# schematic.net
KiCad netlist of a schematic drawn in EAGLE
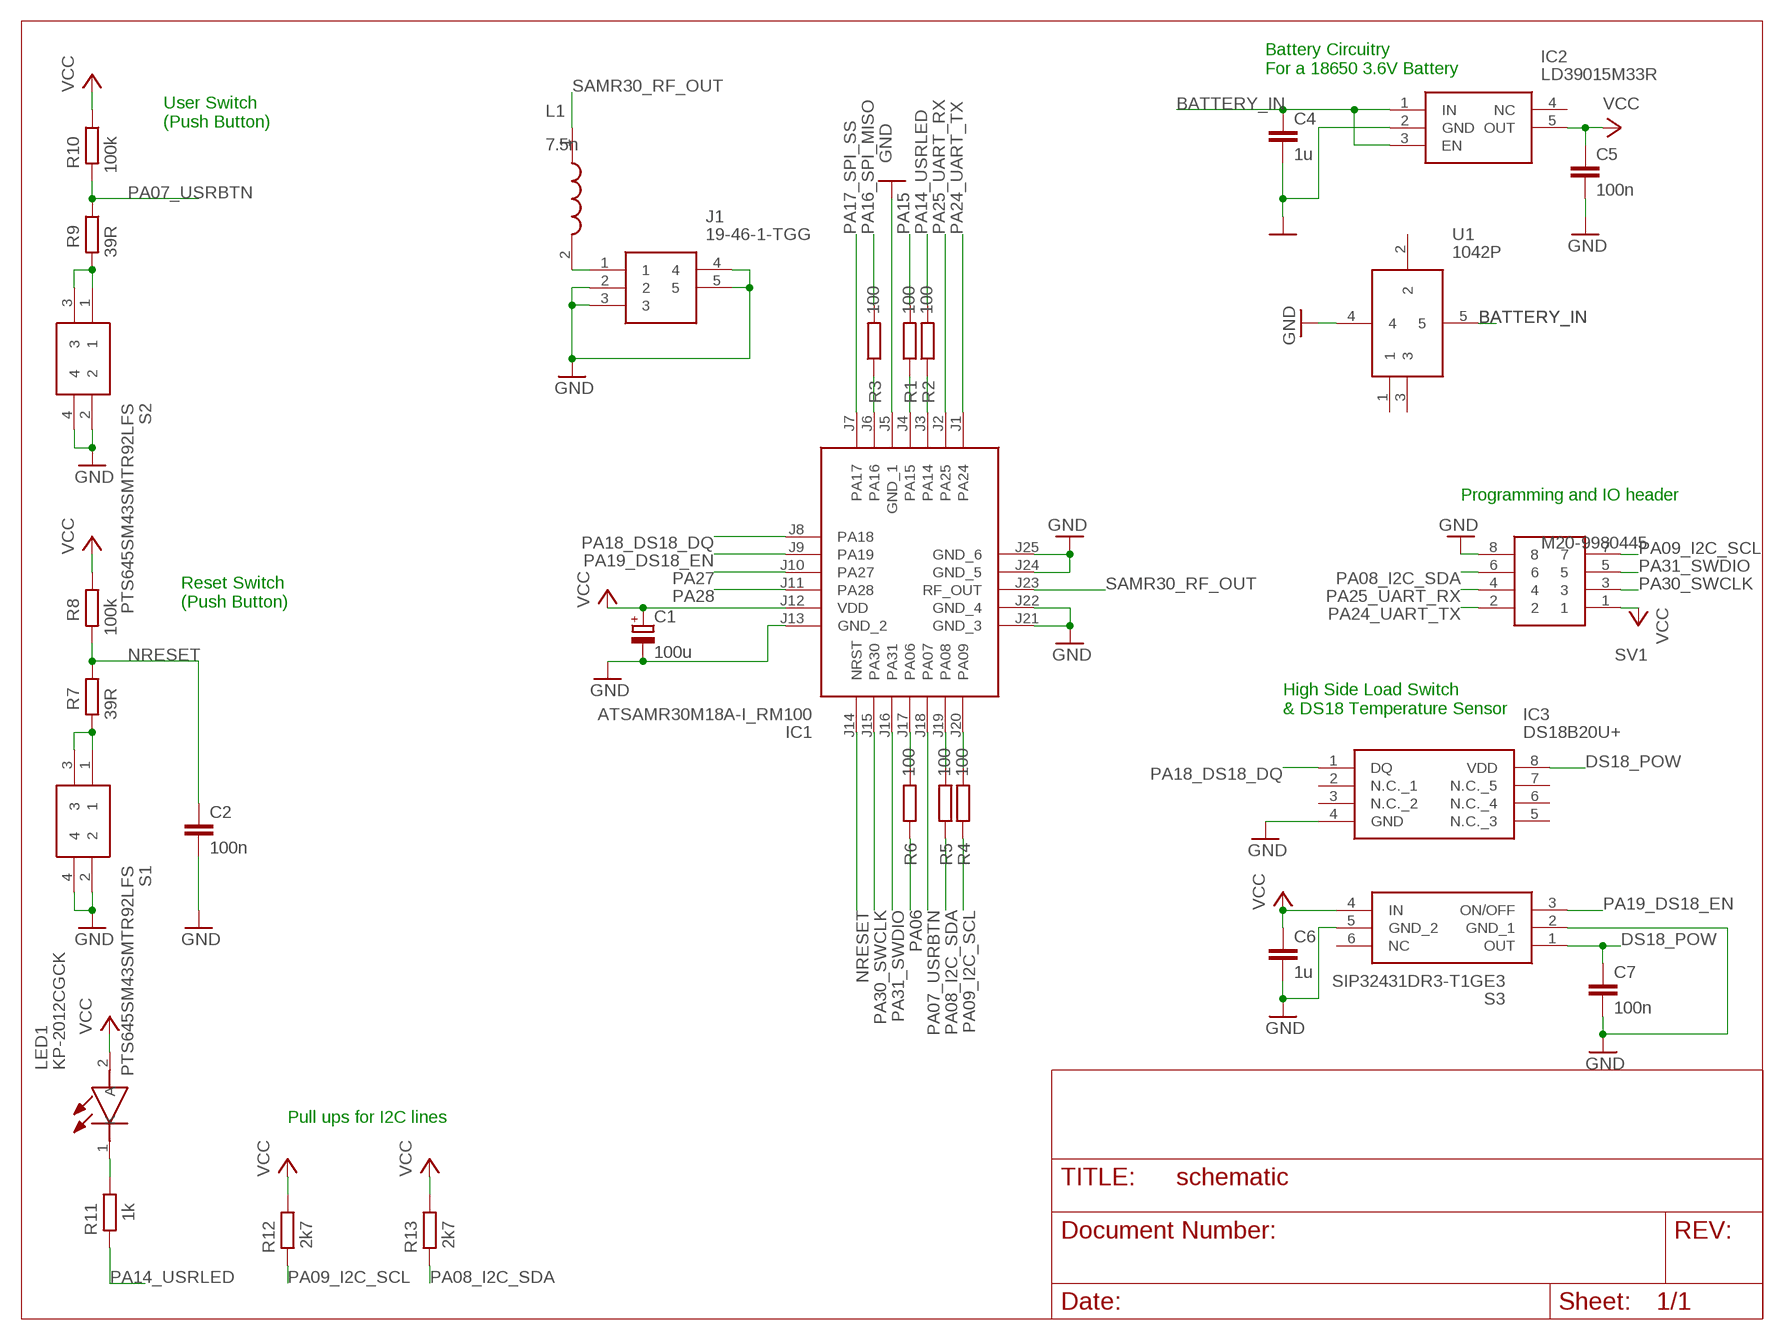
[diagram p0: schematic, sheet 1]

(export (version "E")
  (design (tool "Eeschema 10.0.6"))
  (components
    (comp (ref "C1")
      (value "100u")
      (footprint "eagle-import:A_3216-18W")
      (libsource (lib "eagle-import") (part "CPOL-EUA/3216-18W"))
    )
    (comp (ref "C2")
      (value "100n")
      (footprint "eagle-import:C0805")
      (libsource (lib "eagle-import") (part "C-EUC0805"))
    )
    (comp (ref "C4")
      (value "1u")
      (footprint "eagle-import:C0805")
      (libsource (lib "eagle-import") (part "C-EUC0805"))
    )
    (comp (ref "C5")
      (value "100n")
      (footprint "eagle-import:C0805")
      (libsource (lib "eagle-import") (part "C-EUC0805"))
    )
    (comp (ref "C6")
      (value "1u")
      (footprint "eagle-import:C0805")
      (libsource (lib "eagle-import") (part "C-EUC0805"))
    )
    (comp (ref "C7")
      (value "100n")
      (footprint "eagle-import:C0805")
      (libsource (lib "eagle-import") (part "C-EUC0805"))
    )
    (comp (ref "IC1")
      (value "ATSAMR30M18A-I_RM100")
      (footprint "eagle-import:ATSAMR30M18AIRM100")
      (fields
        (field (name "MANUFACTURER_PART_NUMBER") "ATSAMR30M18A-I/RM100")
        (field (name "MOUSER_PART_NUMBER") "556-AMR30M18AIRM100")
        (field (name "RS_PART_NUMBER") "1840450")
      )
      (libsource (lib "eagle-import") (part "ATSAMR30M18A-I_RM100"))
    )
    (comp (ref "IC2")
      (value "LD39015M33R")
      (footprint "eagle-import:SOT95P280X145-5N")
      (fields
        (field (name "MOUSER_PART_NUMBER") "511-LD39015M33R")
        (field (name "RS_PART_NUMBER") "7958965P")
      )
      (libsource (lib "eagle-import") (part "LD39015M33R"))
    )
    (comp (ref "IC3")
      (value "DS18B20U+")
      (footprint "eagle-import:SOP65P490X110-8N")
      (fields (field (name "MOUSER_PART_NUMBER") "700-DS18B20U"))
      (libsource (lib "eagle-import") (part "DS18B20U+"))
    )
    (comp (ref "J1")
      (value "19-46-1-TGG")
      (footprint "eagle-import:19-46-1-TGG_1")
      (libsource (lib "eagle-import") (part "19-46-1-TGG"))
    )
    (comp (ref "L1")
      (value "7.5n")
      (footprint "eagle-import:INDC1006X60N")
      (fields
        (field (name "MANUFACTURER_PART_NUMBER") "MHQ1005P10NJT")
        (field (name "MOUSER_PART_NUMBER") "810-MHQ1005P10NJT")
        (field (name "RS_PART_NUMBER") "7958243P")
      )
      (libsource (lib "eagle-import") (part "MHQ1005P10NJT"))
    )
    (comp (ref "LED1")
      (value "KP-2012CGCK")
      (footprint "eagle-import:LEDC2012X110N")
      (fields (field (name "RS_PART_NUMBER") "8610037P"))
      (libsource (lib "eagle-import") (part "KP-2012CGCK"))
    )
    (comp (ref "R1")
      (value "100")
      (footprint "eagle-import:R0603")
      (libsource (lib "eagle-import") (part "R-EU_R0603"))
    )
    (comp (ref "R2")
      (value "100")
      (footprint "eagle-import:R0603")
      (libsource (lib "eagle-import") (part "R-EU_R0603"))
    )
    (comp (ref "R3")
      (value "100")
      (footprint "eagle-import:R0603")
      (libsource (lib "eagle-import") (part "R-EU_R0603"))
    )
    (comp (ref "R4")
      (value "100")
      (footprint "eagle-import:R0603")
      (libsource (lib "eagle-import") (part "R-EU_R0603"))
    )
    (comp (ref "R5")
      (value "100")
      (footprint "eagle-import:R0603")
      (libsource (lib "eagle-import") (part "R-EU_R0603"))
    )
    (comp (ref "R6")
      (value "100")
      (footprint "eagle-import:R0603")
      (libsource (lib "eagle-import") (part "R-EU_R0603"))
    )
    (comp (ref "R7")
      (value "39R")
      (footprint "eagle-import:R0603")
      (libsource (lib "eagle-import") (part "R-EU_R0603"))
    )
    (comp (ref "R8")
      (value "100k")
      (footprint "eagle-import:R0603")
      (libsource (lib "eagle-import") (part "R-EU_R0603"))
    )
    (comp (ref "R9")
      (value "39R")
      (footprint "eagle-import:R0603")
      (libsource (lib "eagle-import") (part "R-EU_R0603"))
    )
    (comp (ref "R10")
      (value "100k")
      (footprint "eagle-import:R0603")
      (libsource (lib "eagle-import") (part "R-EU_R0603"))
    )
    (comp (ref "R11")
      (value "1k")
      (footprint "eagle-import:R0603")
      (libsource (lib "eagle-import") (part "R-EU_R0603"))
    )
    (comp (ref "R12")
      (value "2k7")
      (footprint "eagle-import:R0603")
      (libsource (lib "eagle-import") (part "R-EU_R0603"))
    )
    (comp (ref "R13")
      (value "2k7")
      (footprint "eagle-import:R0603")
      (libsource (lib "eagle-import") (part "R-EU_R0603"))
    )
    (comp (ref "S1")
      (value "PTS645SM43SMTR92LFS")
      (footprint "eagle-import:PTS645(SMT)")
      (fields (field (name "MOUSER_PART_NUMBER") "611-PTS645SM43SMTR92"))
      (libsource (lib "eagle-import") (part "PTS645SM43SMTR92LFS"))
    )
    (comp (ref "S2")
      (value "PTS645SM43SMTR92LFS")
      (footprint "eagle-import:PTS645(SMT)")
      (fields (field (name "MOUSER_PART_NUMBER") "611-PTS645SM43SMTR92"))
      (libsource (lib "eagle-import") (part "PTS645SM43SMTR92LFS"))
    )
    (comp (ref "S3")
      (value "SIP32431DR3-T1GE3")
      (footprint "eagle-import:SOT65P210X110-6N")
      (fields
        (field (name "MOUSER_PART_NUMBER") "781-SIP32431DR3-GE3")
        (field (name "RS_PART_NUMBER") "1807353")
      )
      (libsource (lib "eagle-import") (part "SIP32431DR3-T1GE3"))
    )
    (comp (ref "SV1")
      (value "M20-9980445")
      (footprint "eagle-import:HDRV8W64P254_2X4_1016X508X868P")
      (fields
        (field (name "MOUSER_PART_NUMBER") "855-M20-9980445")
        (field (name "RS_PART_NUMBER") "6812941P")
      )
      (libsource (lib "eagle-import") (part "M20-9980445"))
    )
    (comp (ref "U1")
      (value "1042P")
      (footprint "eagle-import:1042P")
      (fields (field (name "MOUSER_PART_NUMBER") "534-1042P"))
      (libsource (lib "eagle-import") (part "1042P"))
    )
  )
  (nets
    (net (code "1") (name "/BATTERY_IN") (class "Default")
      (node (ref "C4") (pin "1") (pinfunction "1_1") (pintype "passive"))
      (node (ref "IC2") (pin "1") (pinfunction "IN_1") (pintype "input"))
      (node (ref "IC2") (pin "3") (pinfunction "EN_3") (pintype "bidirectional"))
      (node (ref "U1") (pin "5") (pinfunction "5_5") (pintype "bidirectional"))
    )
    (net (code "2") (name "/DS18_POW") (class "Default")
      (node (ref "C7") (pin "1") (pinfunction "1_1") (pintype "passive"))
      (node (ref "IC3") (pin "8") (pinfunction "VDD_8") (pintype "power_in"))
      (node (ref "S3") (pin "1") (pinfunction "OUT_1") (pintype "bidirectional"))
    )
    (net (code "3") (name "/NRESET") (class "Default")
      (node (ref "C2") (pin "1") (pinfunction "1_1") (pintype "passive"))
      (node (ref "IC1") (pin "J14") (pinfunction "NRST_J14") (pintype "bidirectional"))
      (node (ref "R7") (pin "1") (pinfunction "1_1") (pintype "passive"))
      (node (ref "R8") (pin "2") (pinfunction "2_2") (pintype "passive"))
    )
    (net (code "4") (name "/PA06") (class "Default")
      (node (ref "R6") (pin "1") (pinfunction "1_1") (pintype "passive"))
    )
    (net (code "5") (name "/PA07_USRBTN") (class "Default")
      (node (ref "IC1") (pin "J18") (pinfunction "PA07_J18") (pintype "bidirectional"))
      (node (ref "R10") (pin "2") (pinfunction "2_2") (pintype "passive"))
      (node (ref "R9") (pin "1") (pinfunction "1_1") (pintype "passive"))
    )
    (net (code "6") (name "/PA08_I2C_SDA") (class "Default")
      (node (ref "R13") (pin "2") (pinfunction "2_2") (pintype "passive"))
      (node (ref "R5") (pin "1") (pinfunction "1_1") (pintype "passive"))
      (node (ref "SV1") (pin "6") (pinfunction "6_6") (pintype "bidirectional"))
    )
    (net (code "7") (name "/PA09_I2C_SCL") (class "Default")
      (node (ref "R12") (pin "2") (pinfunction "2_2") (pintype "passive"))
      (node (ref "R4") (pin "1") (pinfunction "1_1") (pintype "passive"))
      (node (ref "SV1") (pin "7") (pinfunction "7_7") (pintype "bidirectional"))
    )
    (net (code "8") (name "/PA14_USRLED") (class "Default")
      (node (ref "R11") (pin "2") (pinfunction "2_2") (pintype "passive"))
      (node (ref "R2") (pin "2") (pinfunction "2_2") (pintype "passive"))
    )
    (net (code "9") (name "/PA15") (class "Default")
      (node (ref "R1") (pin "2") (pinfunction "2_2") (pintype "passive"))
    )
    (net (code "10") (name "/PA16_SPI_MISO") (class "Default")
      (node (ref "R3") (pin "2") (pinfunction "2_2") (pintype "passive"))
    )
    (net (code "11") (name "/PA17_SPI_SS") (class "Default")
      (node (ref "IC1") (pin "J7") (pinfunction "PA17_J7") (pintype "bidirectional"))
    )
    (net (code "12") (name "/PA18_DS18_DQ") (class "Default")
      (node (ref "IC1") (pin "J8") (pinfunction "PA18_J8") (pintype "bidirectional"))
      (node (ref "IC3") (pin "1") (pinfunction "DQ_1") (pintype "bidirectional"))
    )
    (net (code "13") (name "/PA19_DS18_EN") (class "Default")
      (node (ref "IC1") (pin "J9") (pinfunction "PA19_J9") (pintype "bidirectional"))
      (node (ref "S3") (pin "3") (pinfunction "ON/OFF_3") (pintype "bidirectional"))
    )
    (net (code "14") (name "/PA24_UART_TX") (class "Default")
      (node (ref "IC1") (pin "J1") (pinfunction "PA24_J1") (pintype "bidirectional"))
      (node (ref "SV1") (pin "2") (pinfunction "2_2") (pintype "bidirectional"))
    )
    (net (code "15") (name "/PA25_UART_RX") (class "Default")
      (node (ref "IC1") (pin "J2") (pinfunction "PA25_J2") (pintype "bidirectional"))
      (node (ref "SV1") (pin "4") (pinfunction "4_4") (pintype "bidirectional"))
    )
    (net (code "16") (name "/PA27") (class "Default")
      (node (ref "IC1") (pin "J10") (pinfunction "PA27_J10") (pintype "bidirectional"))
    )
    (net (code "17") (name "/PA28") (class "Default")
      (node (ref "IC1") (pin "J11") (pinfunction "PA28_J11") (pintype "bidirectional"))
    )
    (net (code "18") (name "/PA30_SWCLK") (class "Default")
      (node (ref "IC1") (pin "J15") (pinfunction "PA30_J15") (pintype "bidirectional"))
      (node (ref "SV1") (pin "3") (pinfunction "3_3") (pintype "bidirectional"))
    )
    (net (code "19") (name "/PA31_SWDIO") (class "Default")
      (node (ref "IC1") (pin "J16") (pinfunction "PA31_J16") (pintype "bidirectional"))
      (node (ref "SV1") (pin "5") (pinfunction "5_5") (pintype "bidirectional"))
    )
    (net (code "20") (name "/SAMR30_RF_OUT") (class "Default")
      (node (ref "IC1") (pin "J23") (pinfunction "RF_OUT_J23") (pintype "bidirectional"))
      (node (ref "L1") (pin "1") (pinfunction "1_1") (pintype "bidirectional"))
    )
    (net (code "21") (name "GND") (class "Default")
      (node (ref "C1") (pin "-") (pinfunction "-_-") (pintype "passive"))
      (node (ref "C2") (pin "2") (pinfunction "2_2") (pintype "passive"))
      (node (ref "C4") (pin "2") (pinfunction "2_2") (pintype "passive"))
      (node (ref "C5") (pin "2") (pinfunction "2_2") (pintype "passive"))
      (node (ref "C6") (pin "2") (pinfunction "2_2") (pintype "passive"))
      (node (ref "C7") (pin "2") (pinfunction "2_2") (pintype "passive"))
      (node (ref "IC1") (pin "J13") (pinfunction "GND_2_J13") (pintype "bidirectional"))
      (node (ref "IC1") (pin "J21") (pinfunction "GND_3_J21") (pintype "bidirectional"))
      (node (ref "IC1") (pin "J22") (pinfunction "GND_4_J22") (pintype "bidirectional"))
      (node (ref "IC1") (pin "J24") (pinfunction "GND_5_J24") (pintype "bidirectional"))
      (node (ref "IC1") (pin "J25") (pinfunction "GND_6_J25") (pintype "bidirectional"))
      (node (ref "IC1") (pin "J5") (pinfunction "GND_1_J5") (pintype "bidirectional"))
      (node (ref "IC2") (pin "2") (pinfunction "GND_2") (pintype "power_in"))
      (node (ref "IC3") (pin "4") (pinfunction "GND_4") (pintype "power_in"))
      (node (ref "J1") (pin "2") (pinfunction "2_2") (pintype "bidirectional"))
      (node (ref "J1") (pin "3") (pinfunction "3_3") (pintype "bidirectional"))
      (node (ref "J1") (pin "4") (pinfunction "4_4") (pintype "bidirectional"))
      (node (ref "J1") (pin "5") (pinfunction "5_5") (pintype "bidirectional"))
      (node (ref "S1") (pin "2") (pinfunction "2_2") (pintype "bidirectional"))
      (node (ref "S1") (pin "4") (pinfunction "4_4") (pintype "bidirectional"))
      (node (ref "S2") (pin "2") (pinfunction "2_2") (pintype "bidirectional"))
      (node (ref "S2") (pin "4") (pinfunction "4_4") (pintype "bidirectional"))
      (node (ref "S3") (pin "2") (pinfunction "GND_1_2") (pintype "bidirectional"))
      (node (ref "S3") (pin "5") (pinfunction "GND_2_5") (pintype "bidirectional"))
      (node (ref "SV1") (pin "8") (pinfunction "8_8") (pintype "bidirectional"))
      (node (ref "U1") (pin "4") (pinfunction "4_4") (pintype "bidirectional"))
    )
    (net (code "22") (name "Net-(IC1-PA06)") (class "Default")
      (node (ref "IC1") (pin "J17") (pinfunction "PA06_J17") (pintype "bidirectional"))
      (node (ref "R6") (pin "2") (pinfunction "2_2") (pintype "passive"))
    )
    (net (code "23") (name "Net-(IC1-PA08)") (class "Default")
      (node (ref "IC1") (pin "J19") (pinfunction "PA08_J19") (pintype "bidirectional"))
      (node (ref "R5") (pin "2") (pinfunction "2_2") (pintype "passive"))
    )
    (net (code "24") (name "Net-(IC1-PA09)") (class "Default")
      (node (ref "IC1") (pin "J20") (pinfunction "PA09_J20") (pintype "bidirectional"))
      (node (ref "R4") (pin "2") (pinfunction "2_2") (pintype "passive"))
    )
    (net (code "25") (name "Net-(IC1-PA14)") (class "Default")
      (node (ref "IC1") (pin "J3") (pinfunction "PA14_J3") (pintype "bidirectional"))
      (node (ref "R2") (pin "1") (pinfunction "1_1") (pintype "passive"))
    )
    (net (code "26") (name "Net-(IC1-PA15)") (class "Default")
      (node (ref "IC1") (pin "J4") (pinfunction "PA15_J4") (pintype "bidirectional"))
      (node (ref "R1") (pin "1") (pinfunction "1_1") (pintype "passive"))
    )
    (net (code "27") (name "Net-(IC1-PA16)") (class "Default")
      (node (ref "IC1") (pin "J6") (pinfunction "PA16_J6") (pintype "bidirectional"))
      (node (ref "R3") (pin "1") (pinfunction "1_1") (pintype "passive"))
    )
    (net (code "28") (name "Net-(J1-Pad1)") (class "Default")
      (node (ref "J1") (pin "1") (pinfunction "1_1") (pintype "bidirectional"))
      (node (ref "L1") (pin "2") (pinfunction "2_2") (pintype "bidirectional"))
    )
    (net (code "29") (name "Net-(LED1-K)") (class "Default")
      (node (ref "LED1") (pin "1") (pinfunction "K_1") (pintype "bidirectional"))
      (node (ref "R11") (pin "1") (pinfunction "1_1") (pintype "passive"))
    )
    (net (code "30") (name "Net-(R7-Pad2)") (class "Default")
      (node (ref "R7") (pin "2") (pinfunction "2_2") (pintype "passive"))
      (node (ref "S1") (pin "1") (pinfunction "1_1") (pintype "bidirectional"))
      (node (ref "S1") (pin "3") (pinfunction "3_3") (pintype "bidirectional"))
    )
    (net (code "31") (name "Net-(R9-Pad2)") (class "Default")
      (node (ref "R9") (pin "2") (pinfunction "2_2") (pintype "passive"))
      (node (ref "S2") (pin "1") (pinfunction "1_1") (pintype "bidirectional"))
      (node (ref "S2") (pin "3") (pinfunction "3_3") (pintype "bidirectional"))
    )
    (net (code "32") (name "VCC") (class "Default")
      (node (ref "C1") (pin "+") (pinfunction "+_+") (pintype "passive"))
      (node (ref "C5") (pin "1") (pinfunction "1_1") (pintype "passive"))
      (node (ref "C6") (pin "1") (pinfunction "1_1") (pintype "passive"))
      (node (ref "IC1") (pin "J12") (pinfunction "VDD_J12") (pintype "bidirectional"))
      (node (ref "IC2") (pin "5") (pinfunction "OUT_5") (pintype "output"))
      (node (ref "LED1") (pin "2") (pinfunction "A_2") (pintype "bidirectional"))
      (node (ref "R10") (pin "1") (pinfunction "1_1") (pintype "passive"))
      (node (ref "R12") (pin "1") (pinfunction "1_1") (pintype "passive"))
      (node (ref "R13") (pin "1") (pinfunction "1_1") (pintype "passive"))
      (node (ref "R8") (pin "1") (pinfunction "1_1") (pintype "passive"))
      (node (ref "S3") (pin "4") (pinfunction "IN_4") (pintype "bidirectional"))
      (node (ref "SV1") (pin "1") (pinfunction "1_1") (pintype "bidirectional"))
    )
    (net (code "33") (name "unconnected-(IC2-NC-Pad4)") (class "Default")
      (node (ref "IC2") (pin "4") (pinfunction "NC_4") (pintype "no_connect"))
    )
    (net (code "34") (name "unconnected-(IC3-N.C._1-Pad2)") (class "Default")
      (node (ref "IC3") (pin "2") (pinfunction "N.C._1_2") (pintype "bidirectional"))
    )
    (net (code "35") (name "unconnected-(IC3-N.C._2-Pad3)") (class "Default")
      (node (ref "IC3") (pin "3") (pinfunction "N.C._2_3") (pintype "bidirectional"))
    )
    (net (code "36") (name "unconnected-(IC3-N.C._3-Pad5)") (class "Default")
      (node (ref "IC3") (pin "5") (pinfunction "N.C._3_5") (pintype "bidirectional"))
    )
    (net (code "37") (name "unconnected-(IC3-N.C._4-Pad6)") (class "Default")
      (node (ref "IC3") (pin "6") (pinfunction "N.C._4_6") (pintype "bidirectional"))
    )
    (net (code "38") (name "unconnected-(IC3-N.C._5-Pad7)") (class "Default")
      (node (ref "IC3") (pin "7") (pinfunction "N.C._5_7") (pintype "bidirectional"))
    )
    (net (code "39") (name "unconnected-(S3-NC-Pad6)") (class "Default")
      (node (ref "S3") (pin "6") (pinfunction "NC_6") (pintype "no_connect"))
    )
    (net (code "40") (name "unconnected-(U1-Pad1)") (class "Default")
      (node (ref "U1") (pin "1") (pinfunction "1_1") (pintype "bidirectional"))
    )
    (net (code "41") (name "unconnected-(U1-Pad2)") (class "Default")
      (node (ref "U1") (pin "2") (pinfunction "2_2") (pintype "bidirectional"))
    )
    (net (code "42") (name "unconnected-(U1-Pad3)") (class "Default")
      (node (ref "U1") (pin "3") (pinfunction "3_3") (pintype "bidirectional"))
    )
  )
)
